# USB_Type_C.net
KiCad netlist of a schematic drawn in Altium Designer
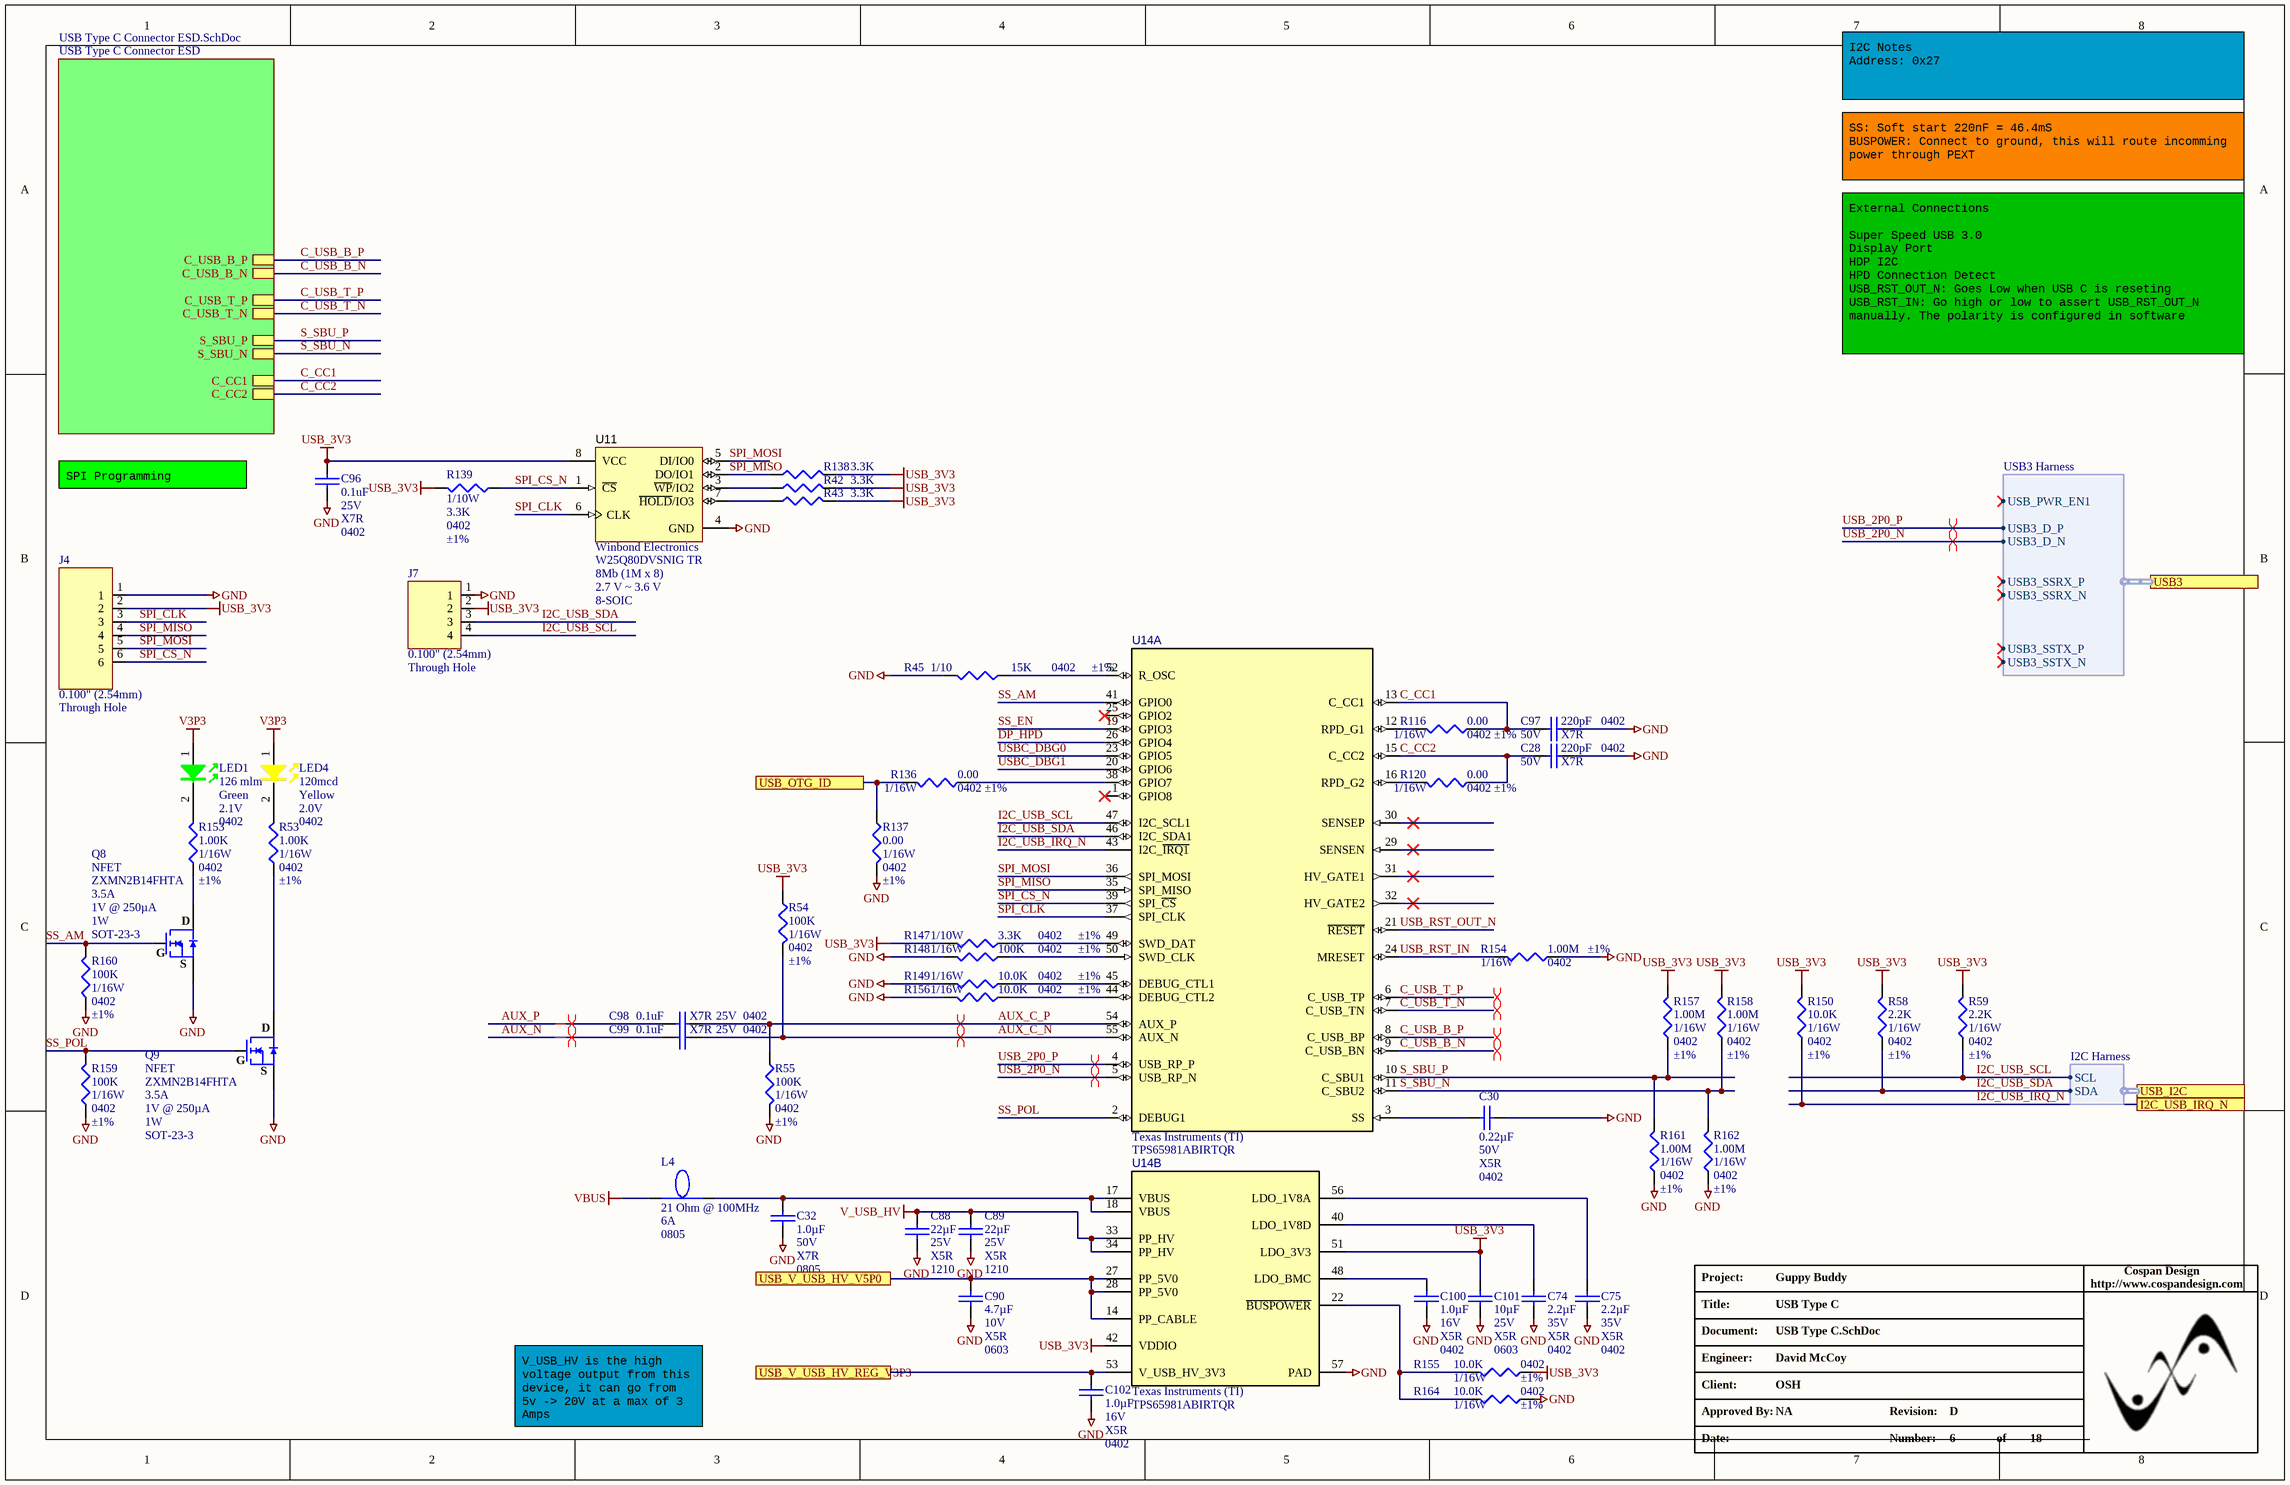
[diagram p0: USB Type C.SchDoc]

(export (version "E")
  (design (tool "Eeschema 10.0.6"))
  (components
    (comp (ref "C28")
      (value "220pF")
      (footprint "C_0402")
      (description "CAP CER 220PF 50V 10% X7R 0402")
      (fields
        (field (name "MANUFACTURER") "Murata Electronics North America")
        (field (name "MANUFACTURER PART NUMBER") "GRM155R71H221KA01D")
        (field (name "CAPACITANCE") "220pF")
        (field (name "VOLTAGE - RATED") "50V")
        (field (name "TEMPERATURE COEFFICIENT") "X7R")
        (field (name "PACKAGE / CASE") "0402")
      )
      (libsource (lib "Main Library") (part "C_0402_220PF_50V"))
    )
    (comp (ref "C30")
      (value "C_0402_0.22UF_50V")
      (footprint "C_ERA-0402")
      (description "CAP CER 0.22UF 50V X5R 0402")
      (fields
        (field (name "MANUFACTURER") "Taiyo Yuden")
        (field (name "MANUFACTURER PART NUMBER") "UMK105BJ224KV-F")
        (field (name "CAPACITANCE") "0.22µF")
        (field (name "VOLTAGE - RATED") "50V")
        (field (name "TEMPERATURE COEFFICIENT") "X5R")
        (field (name "PACKAGE / CASE") "0402")
      )
      (libsource (lib "Main Library") (part "C_0402_0.22UF_50V"))
    )
    (comp (ref "C32")
      (value "1.0uF")
      (footprint "C_ERA-0805")
      (description "CAP CER 1UF 50V X7R 0805")
      (fields
        (field (name "TOLERANCE") "10%")
        (field (name "CAPACITANCE") "1.0µF")
        (field (name "VOLTAGE - RATED") "50V")
        (field (name "TEMPERATURE COEFFICIENT") "X7R")
        (field (name "PACKAGE / CASE") "0805")
        (field (name "VOLTAGE") "50V")
      )
      (libsource (lib "Main LibraryX") (part "C_0805_1.0uF_50V"))
    )
    (comp (ref "C74")
      (value "C_0402_2.2uF_35V")
      (footprint "C_ERA-0402")
      (description "CAP CER 2.2UF 35V 20% X5R 0402")
      (fields
        (field (name "MANUFACTURER") "TDK Corporation")
        (field (name "MANUFACTURER PART NUMBER") "C1005X5R1V225K050BC")
        (field (name "CAPACITANCE") "2.2µF")
        (field (name "VOLTAGE - RATED") "35V")
        (field (name "TEMPERATURE COEFFICIENT") "X5R")
        (field (name "PACKAGE / CASE") "0402")
      )
      (libsource (lib "Main Library") (part "C_0402_2.2uF_35V"))
    )
    (comp (ref "C75")
      (value "C_0402_2.2uF_35V")
      (footprint "C_ERA-0402")
      (description "CAP CER 2.2UF 35V 20% X5R 0402")
      (fields
        (field (name "MANUFACTURER") "TDK Corporation")
        (field (name "MANUFACTURER PART NUMBER") "C1005X5R1V225K050BC")
        (field (name "CAPACITANCE") "2.2µF")
        (field (name "VOLTAGE - RATED") "35V")
        (field (name "TEMPERATURE COEFFICIENT") "X5R")
        (field (name "PACKAGE / CASE") "0402")
      )
      (libsource (lib "Main Library") (part "C_0402_2.2uF_35V"))
    )
    (comp (ref "C88")
      (value "22µF")
      (footprint "C_14-1210")
      (description "CAP CER 22UF 25V 20% X5R 1210")
      (fields
        (field (name "MANUFACTURER") "Taiyo Yuden")
        (field (name "MANUFACTURER PART NUMBER") "TMK325BJ226MM-T")
        (field (name "CAPACITANCE") "22µF")
        (field (name "VOLTAGE - RATED") "25V")
        (field (name "TEMPERATURE COEFFICIENT") "X5R")
        (field (name "PACKAGE / CASE") "1210")
      )
      (libsource (lib "Main Library") (part "C_1210_22µF"))
    )
    (comp (ref "C89")
      (value "22µF")
      (footprint "C_14-1210")
      (description "CAP CER 22UF 25V 20% X5R 1210")
      (fields
        (field (name "MANUFACTURER") "Taiyo Yuden")
        (field (name "MANUFACTURER PART NUMBER") "TMK325BJ226MM-T")
        (field (name "CAPACITANCE") "22µF")
        (field (name "VOLTAGE - RATED") "25V")
        (field (name "TEMPERATURE COEFFICIENT") "X5R")
        (field (name "PACKAGE / CASE") "1210")
      )
      (libsource (lib "Main Library") (part "C_1210_22µF"))
    )
    (comp (ref "C90")
      (value "4.7µF")
      (footprint "C_0603")
      (description "CAP CER 4.7UF 10V X5R 0603")
      (fields
        (field (name "TOLERANCE") "10%")
        (field (name "CAPACITANCE") "4.7µF")
        (field (name "VOLTAGE - RATED") "10V")
        (field (name "TEMPERATURE COEFFICIENT") "X5R")
        (field (name "PACKAGE / CASE") "0603")
        (field (name "VOLTAGE") "35V")
      )
      (libsource (lib "Main LibraryX") (part "C_0603_4.7uF_10V"))
    )
    (comp (ref "C96")
      (value "C_0402_0.1UF_25V")
      (footprint "C_0402")
      (description "CAP CER 0.1UF 25V X6S 0402")
      (fields
        (field (name "TOLERANCE") "10%")
        (field (name "CAPACITANCE") "0.1uF")
        (field (name "VOLTAGE - RATED") "25V")
        (field (name "TEMPERATURE COEFFICIENT") "X7R")
        (field (name "PACKAGE / CASE") "0402")
      )
      (libsource (lib "Cospan Design") (part "C_0402_0.1UF_25V"))
    )
    (comp (ref "C97")
      (value "220pF")
      (footprint "C_0402")
      (description "CAP CER 220PF 50V 10% X7R 0402")
      (fields
        (field (name "MANUFACTURER") "Murata Electronics North America")
        (field (name "MANUFACTURER PART NUMBER") "GRM155R71H221KA01D")
        (field (name "CAPACITANCE") "220pF")
        (field (name "VOLTAGE - RATED") "50V")
        (field (name "TEMPERATURE COEFFICIENT") "X7R")
        (field (name "PACKAGE / CASE") "0402")
      )
      (libsource (lib "Main Library") (part "C_0402_220PF_50V"))
    )
    (comp (ref "C98")
      (value "C_0402_0.1UF_25V")
      (footprint "C_0402")
      (description "CAP CER 0.1UF 25V X6S 0402")
      (fields
        (field (name "TOLERANCE") "10%")
        (field (name "CAPACITANCE") "0.1uF")
        (field (name "VOLTAGE - RATED") "25V")
        (field (name "TEMPERATURE COEFFICIENT") "X7R")
        (field (name "PACKAGE / CASE") "0402")
      )
      (libsource (lib "Cospan Design") (part "C_0402_0.1UF_25V"))
    )
    (comp (ref "C99")
      (value "C_0402_0.1UF_25V")
      (footprint "C_0402")
      (description "CAP CER 0.1UF 25V X6S 0402")
      (fields
        (field (name "TOLERANCE") "10%")
        (field (name "CAPACITANCE") "0.1uF")
        (field (name "VOLTAGE - RATED") "25V")
        (field (name "TEMPERATURE COEFFICIENT") "X7R")
        (field (name "PACKAGE / CASE") "0402")
      )
      (libsource (lib "Cospan Design") (part "C_0402_0.1UF_25V"))
    )
    (comp (ref "C100")
      (value "1.0uF")
      (footprint "C_0402")
      (description "CAP CER 1.0UF 16V X5R 0402")
      (fields
        (field (name "TOLERANCE") "10%")
        (field (name "CAPACITANCE") "1.0µF")
        (field (name "VOLTAGE - RATED") "16V")
        (field (name "TEMPERATURE COEFFICIENT") "X5R")
        (field (name "PACKAGE / CASE") "0402")
        (field (name "VOLTAGE") "16V")
      )
      (libsource (lib "Main LibraryX") (part "C_0402_1.0UF_16V"))
    )
    (comp (ref "C101")
      (value "C_0603_10µF")
      (footprint "C_ERA-0603")
      (description "CAP CER 10UF 16V X5R 0603")
      (fields
        (field (name "MANUFACTURER") "Murata Electronics North America")
        (field (name "MANUFACTURER PART NUMBER") "GRM188R61C106MA73D")
        (field (name "CAPACITANCE") "10µF")
        (field (name "VOLTAGE - RATED") "25V")
        (field (name "TEMPERATURE COEFFICIENT") "X5R")
        (field (name "PACKAGE / CASE") "0603")
      )
      (libsource (lib "Cospan Design") (part "C_0603_10µF"))
    )
    (comp (ref "C102")
      (value "1.0uF")
      (footprint "C_0402")
      (description "CAP CER 1.0UF 16V X5R 0402")
      (fields
        (field (name "TOLERANCE") "10%")
        (field (name "CAPACITANCE") "1.0µF")
        (field (name "VOLTAGE - RATED") "16V")
        (field (name "TEMPERATURE COEFFICIENT") "X5R")
        (field (name "PACKAGE / CASE") "0402")
        (field (name "VOLTAGE") "16V")
      )
      (libsource (lib "Main LibraryX") (part "C_0402_1.0UF_16V"))
    )
    (comp (ref "J4")
      (value "J_HDR1X6_THRHOLE_VERT")
      (footprint "HDR_1X6")
      (description "CONN HEADER .100\" 12POS TIN PCB")
      (fields
        (field (name "MANUFACTURER") "Samtec")
        (field (name "MANUFACTURER PART NUMBER") "TSW-106-07-T-S")
        (field (name "PITCH") "0.100\" (2.54mm)")
        (field (name "MOUNTING TYPE") "Through Hole")
      )
      (libsource (lib "Main Library") (part "J_HDR1X6_THRHOLE_VERT"))
    )
    (comp (ref "J7")
      (value "J_HDR1X4_THRHOLE_VERT")
      (footprint "HDR_1X4")
      (description "CONN HEADER .100\" 4POS TIN PCB")
      (fields
        (field (name "MANUFACTURER") "Samtec")
        (field (name "MANUFACTURER PART NUMBER") "TSW-104-07-T-S")
        (field (name "PITCH") "0.100\" (2.54mm)")
        (field (name "MOUNTING TYPE") "Through Hole")
      )
      (libsource (lib "Main Library") (part "J_HDR1X4_THRHOLE_VERT"))
    )
    (comp (ref "L4")
      (value "L_FB_21OHM_100MHZ")
      (footprint "C_ERA-0805")
      (description "FERRITE BEAD 21 OHM 0805 1LN")
      (fields
        (field (name "MANUFACTURER") "Taiyo Yuden")
        (field (name "MANUFACTURER PART NUMBER") "FBMJ2125HM210NT")
        (field (name "IMPEDANCE @ FREQUENCY") "21 Ohm @ 100MHz")
        (field (name "CURRENT RATING") "6A")
        (field (name "PACKAGE / CASE") "0805")
      )
      (libsource (lib "Main Library") (part "L_FB_21OHM_100MHZ"))
    )
    (comp (ref "LED1")
      (value "LED_GRN_0402")
      (footprint "DIOM1005X07L_GREEN")
      (description "LED 1X0.5MM 570NM GN WTR CLR SMD")
      (fields
        (field (name "MANUFACTURER") "Kingbright Corp")
        (field (name "MANUFACTURER PART NUMBER") "APHHS1005CGCK")
        (field (name "LUMINOUS FLUX @ CURRENT - TEST") "126 mlm")
        (field (name "COLOR") "Green")
        (field (name "VOLTAGE - FORWARD (VF) TYP") "2.1V")
        (field (name "PACKAGE / CASE") "0402")
      )
      (libsource (lib "Main Library") (part "LED_GRN_0402"))
    )
    (comp (ref "LED4")
      (value "LED_YLW_0402")
      (footprint "DIOM1005X07L_YELLOW")
      (description "LED 1X0.5MM 590NM YW WTR CLR SMD")
      (fields
        (field (name "MANUFACTURER") "Kingbright Corp")
        (field (name "MANUFACTURER PART NUMBER") "APHHS1005SYCK")
        (field (name "MILLICANDELA RATING") "120mcd")
        (field (name "COLOR") "Yellow")
        (field (name "VOLTAGE - FORWARD (VF) TYP") "2.0V")
        (field (name "PACKAGE / CASE") "0402")
      )
      (libsource (lib "Main Library") (part "LED_YLW_0402"))
    )
    (comp (ref "Q8")
      (value "NFET")
      (footprint "SOT-23A")
      (description "MOSFET N-CH 20V 3.5A SOT23-3")
      (fields
        (field (name "MANUFACTURER") "Diodes Incorporated")
        (field (name "MANUFACTURER PART NUMBER") "ZXMN2B14FHTA")
        (field (name "CURRENT - CONTINUOUS DRAIN (ID) @ 25° C") "3.5A")
        (field (name "VGS(TH) (MAX) @ ID") "1V @ 250µA")
        (field (name "POWER - MAX") "1W")
        (field (name "PACKAGE / CASE") "SOT-23-3")
      )
      (libsource (lib "Main LibraryX") (part "Q_NFET_3.50A_SOT23"))
    )
    (comp (ref "Q9")
      (value "NFET")
      (footprint "SOT-23A")
      (description "MOSFET N-CH 20V 3.5A SOT23-3")
      (fields
        (field (name "MANUFACTURER") "Diodes Incorporated")
        (field (name "MANUFACTURER PART NUMBER") "ZXMN2B14FHTA")
        (field (name "CURRENT - CONTINUOUS DRAIN (ID) @ 25° C") "3.5A")
        (field (name "VGS(TH) (MAX) @ ID") "1V @ 250µA")
        (field (name "POWER - MAX") "1W")
        (field (name "PACKAGE / CASE") "SOT-23-3")
      )
      (libsource (lib "Main LibraryX") (part "Q_NFET_3.50A_SOT23"))
    )
    (comp (ref "R42")
      (value "3.3k Ohms")
      (footprint "R_0402")
      (description "RES 3.30K OHM 1/10W 1% 0402 SM")
      (fields
        (field (name "MANUFACTURER") "Panasonic - ECG")
        (field (name "MANUFACTURER PART NUMBER") "ERJ-2RKF3301X")
        (field (name "RESISTANCE IN OHMS") "3.3K")
      )
      (libsource (lib "Main Library") (part "R_0402_3.3K"))
    )
    (comp (ref "R43")
      (value "3.3k Ohms")
      (footprint "R_0402")
      (description "RES 3.30K OHM 1/10W 1% 0402 SM")
      (fields
        (field (name "MANUFACTURER") "Panasonic - ECG")
        (field (name "MANUFACTURER PART NUMBER") "ERJ-2RKF3301X")
        (field (name "RESISTANCE IN OHMS") "3.3K")
      )
      (libsource (lib "Main Library") (part "R_0402_3.3K"))
    )
    (comp (ref "R45")
      (value "R_0402_15.0K")
      (footprint "R_0402")
      (description "RES 15.0K OHM 1/10W 1% 0402 SMD")
      (fields
        (field (name "MANUFACTURER") "Panasonic - ECG")
        (field (name "MANUFACTURER PART NUMBER") "ERJ-2RKF1502X")
        (field (name "RESISTANCE IN OHMS") "15K")
        (field (name "POWER (WATTS)") "1/10")
        (field (name "CASE") "0402")
        (field (name "TOLERANCE") "±1%")
      )
      (libsource (lib "Main Library") (part "R_0402_15.0K"))
    )
    (comp (ref "R53")
      (value "1.0k Ohms")
      (footprint "R_0402")
      (description "RES 1.00K OHM 1/16W 1% 0402 SMD")
      (fields
        (field (name "MANUFACTURER") "Yageo")
        (field (name "MANUFACTURER PART NUMBER") "RC0402FR-071KL")
        (field (name "RESISTANCE IN OHMS") "1.00K")
        (field (name "POWER (WATTS)") "1/16W")
        (field (name "CASE") "0402")
        (field (name "TOLERANCE") "±1%")
      )
      (libsource (lib "Main Library") (part "R_0402_1.0K"))
    )
    (comp (ref "R54")
      (value "R_0402_100K")
      (footprint "R_0402")
      (description "RES SMD 100K OHM 1% 1/16W 0402")
      (fields
        (field (name "MANUFACTURER") "Yageo")
        (field (name "MANUFACTURER PART NUMBER") "RC0402FR-07100KL")
        (field (name "RESISTANCE IN OHMS") "100K")
        (field (name "POWER (WATTS)") "1/16W")
        (field (name "CASE") "0402")
        (field (name "TOLERANCE") "±1%")
      )
      (libsource (lib "Cospan Design") (part "R_0402_100K"))
    )
    (comp (ref "R55")
      (value "R_0402_100K")
      (footprint "R_0402")
      (description "RES SMD 100K OHM 1% 1/16W 0402")
      (fields
        (field (name "MANUFACTURER") "Yageo")
        (field (name "MANUFACTURER PART NUMBER") "RC0402FR-07100KL")
        (field (name "RESISTANCE IN OHMS") "100K")
        (field (name "POWER (WATTS)") "1/16W")
        (field (name "CASE") "0402")
        (field (name "TOLERANCE") "±1%")
      )
      (libsource (lib "Cospan Design") (part "R_0402_100K"))
    )
    (comp (ref "R58")
      (value "R_0402_2.2K")
      (footprint "R_0402")
      (description "RES SMD 2.2K OHM 1% 1/10W 0402")
      (fields
        (field (name "MANUFACTURER") "Panasonic Electronic Components")
        (field (name "MANUFACTURER PART NUMBER") "ERJ-2RKF2201X")
        (field (name "RESISTANCE IN OHMS") "2.2K")
        (field (name "POWER (WATTS)") "1/16W")
        (field (name "CASE") "0402")
        (field (name "TOLERANCE") "±1%")
      )
      (libsource (lib "Cospan Design") (part "R_0402_2.2K"))
    )
    (comp (ref "R59")
      (value "R_0402_2.2K")
      (footprint "R_0402")
      (description "RES SMD 2.2K OHM 1% 1/10W 0402")
      (fields
        (field (name "MANUFACTURER") "Panasonic Electronic Components")
        (field (name "MANUFACTURER PART NUMBER") "ERJ-2RKF2201X")
        (field (name "RESISTANCE IN OHMS") "2.2K")
        (field (name "POWER (WATTS)") "1/16W")
        (field (name "CASE") "0402")
        (field (name "TOLERANCE") "±1%")
      )
      (libsource (lib "Cospan Design") (part "R_0402_2.2K"))
    )
    (comp (ref "R116")
      (value "0.0 Ohms")
      (footprint "R_0402")
      (description "RES 0.00 OHM 1/16W 1% 0402 SMD")
      (fields
        (field (name "MANUFACTURER") "Yageo")
        (field (name "MANUFACTURER PART NUMBER") "RC0402JR-070RL")
        (field (name "RESISTANCE IN OHMS") "0.00")
        (field (name "POWER (WATTS)") "1/16W")
        (field (name "CASE") "0402")
        (field (name "TOLERANCE") "±1%")
      )
      (libsource (lib "Cospan Design") (part "R_0402_0.00"))
    )
    (comp (ref "R120")
      (value "0.0 Ohms")
      (footprint "R_0402")
      (description "RES 0.00 OHM 1/16W 1% 0402 SMD")
      (fields
        (field (name "MANUFACTURER") "Yageo")
        (field (name "MANUFACTURER PART NUMBER") "RC0402JR-070RL")
        (field (name "RESISTANCE IN OHMS") "0.00")
        (field (name "POWER (WATTS)") "1/16W")
        (field (name "CASE") "0402")
        (field (name "TOLERANCE") "±1%")
      )
      (libsource (lib "Cospan Design") (part "R_0402_0.00"))
    )
    (comp (ref "R136")
      (value "0.0 Ohms")
      (footprint "R_0402")
      (description "RES 0.00 OHM 1/16W 1% 0402 SMD")
      (fields
        (field (name "MANUFACTURER") "Yageo")
        (field (name "MANUFACTURER PART NUMBER") "RC0402JR-070RL")
        (field (name "RESISTANCE IN OHMS") "0.00")
        (field (name "POWER (WATTS)") "1/16W")
        (field (name "CASE") "0402")
        (field (name "TOLERANCE") "±1%")
      )
      (libsource (lib "Cospan Design") (part "R_0402_0.00"))
    )
    (comp (ref "R137")
      (value "0.0 Ohms")
      (footprint "R_0402")
      (description "RES 0.00 OHM 1/16W 1% 0402 SMD")
      (fields
        (field (name "MANUFACTURER") "Yageo")
        (field (name "MANUFACTURER PART NUMBER") "RC0402JR-070RL")
        (field (name "RESISTANCE IN OHMS") "0.00")
        (field (name "POWER (WATTS)") "1/16W")
        (field (name "CASE") "0402")
        (field (name "TOLERANCE") "±1%")
      )
      (libsource (lib "Cospan Design") (part "R_0402_0.00"))
    )
    (comp (ref "R138")
      (value "3.3k Ohms")
      (footprint "R_0402")
      (description "RES 3.30K OHM 1/10W 1% 0402 SM")
      (fields
        (field (name "MANUFACTURER") "Panasonic - ECG")
        (field (name "MANUFACTURER PART NUMBER") "ERJ-2RKF3301X")
        (field (name "RESISTANCE IN OHMS") "3.3K")
      )
      (libsource (lib "Main Library") (part "R_0402_3.3K"))
    )
    (comp (ref "R139")
      (value "3.3k Ohms")
      (footprint "R_0402")
      (description "RES 3.30K OHM 1/10W 1% 0402 SM")
      (fields
        (field (name "MANUFACTURER") "Panasonic - ECG")
        (field (name "MANUFACTURER PART NUMBER") "ERJ-2RKF3301X")
        (field (name "POWER (WATTS)") "1/10W")
        (field (name "RESISTANCE IN OHMS") "3.3K")
        (field (name "CASE") "0402")
        (field (name "TOLERANCE") "±1%")
      )
      (libsource (lib "Main Library") (part "R_0402_3.3K"))
    )
    (comp (ref "R147")
      (value "3.3k Ohms")
      (footprint "R_0402")
      (description "RES 3.30K OHM 1/10W 1% 0402 SM")
      (fields
        (field (name "MANUFACTURER") "Panasonic - ECG")
        (field (name "MANUFACTURER PART NUMBER") "ERJ-2RKF3301X")
        (field (name "POWER (WATTS)") "1/10W")
        (field (name "RESISTANCE IN OHMS") "3.3K")
        (field (name "CASE") "0402")
        (field (name "TOLERANCE") "±1%")
      )
      (libsource (lib "Main Library") (part "R_0402_3.3K"))
    )
    (comp (ref "R148")
      (value "R_0402_100K")
      (footprint "R_0402")
      (description "RES SMD 100K OHM 1% 1/16W 0402")
      (fields
        (field (name "MANUFACTURER") "Yageo")
        (field (name "MANUFACTURER PART NUMBER") "RC0402FR-07100KL")
        (field (name "RESISTANCE IN OHMS") "100K")
        (field (name "POWER (WATTS)") "1/16W")
        (field (name "CASE") "0402")
        (field (name "TOLERANCE") "±1%")
      )
      (libsource (lib "Cospan Design") (part "R_0402_100K"))
    )
    (comp (ref "R149")
      (value "R_0402_10.0K")
      (footprint "R_0402")
      (description "RES 10.0K OHM 1/16W 1% 0402 SMD")
      (fields
        (field (name "MANUFACTURER") "Stackpole Electronics Inc")
        (field (name "MANUFACTURER PART NUMBER") "RMCF0402FT10K0")
        (field (name "RESISTANCE IN OHMS") "10.0K")
        (field (name "POWER (WATTS)") "1/16W")
        (field (name "CASE") "0402")
        (field (name "TOLERANCE") "±1%")
      )
      (libsource (lib "Cospan Design") (part "R_0402_10.0K"))
    )
    (comp (ref "R150")
      (value "R_0402_10.0K")
      (footprint "R_0402")
      (description "RES 10.0K OHM 1/16W 1% 0402 SMD")
      (fields
        (field (name "MANUFACTURER") "Stackpole Electronics Inc")
        (field (name "MANUFACTURER PART NUMBER") "RMCF0402FT10K0")
        (field (name "RESISTANCE IN OHMS") "10.0K")
        (field (name "POWER (WATTS)") "1/16W")
        (field (name "CASE") "0402")
        (field (name "TOLERANCE") "±1%")
      )
      (libsource (lib "Cospan Design") (part "R_0402_10.0K"))
    )
    (comp (ref "R153")
      (value "1.0k Ohms")
      (footprint "R_0402")
      (description "RES 1.00K OHM 1/16W 1% 0402 SMD")
      (fields
        (field (name "MANUFACTURER") "Yageo")
        (field (name "MANUFACTURER PART NUMBER") "RC0402FR-071KL")
        (field (name "RESISTANCE IN OHMS") "1.00K")
        (field (name "POWER (WATTS)") "1/16W")
        (field (name "CASE") "0402")
        (field (name "TOLERANCE") "±1%")
      )
      (libsource (lib "Main Library") (part "R_0402_1.0K"))
    )
    (comp (ref "R154")
      (value "1.0M Ohms")
      (footprint "R_0402")
      (description "RES 1.00M OHM 1/16W 1% 0402 SMD")
      (fields
        (field (name "MANUFACTURER") "Vishay/Dale")
        (field (name "MANUFACTURER PART NUMBER") "CRCW04021M00FKED")
        (field (name "RESISTANCE IN OHMS") "1.00M")
        (field (name "POWER (WATTS)") "1/16W")
        (field (name "CASE") "0402")
        (field (name "TOLERANCE") "±1%")
      )
      (libsource (lib "Main Library") (part "R_0402_1.0M"))
    )
    (comp (ref "R155")
      (value "R_0402_10.0K")
      (footprint "R_0402")
      (description "RES 10.0K OHM 1/16W 1% 0402 SMD")
      (fields
        (field (name "MANUFACTURER") "Stackpole Electronics Inc")
        (field (name "MANUFACTURER PART NUMBER") "RMCF0402FT10K0")
        (field (name "RESISTANCE IN OHMS") "10.0K")
        (field (name "POWER (WATTS)") "1/16W")
        (field (name "CASE") "0402")
        (field (name "TOLERANCE") "±1%")
      )
      (libsource (lib "Cospan Design") (part "R_0402_10.0K"))
    )
    (comp (ref "R156")
      (value "R_0402_10.0K")
      (footprint "R_0402")
      (description "RES 10.0K OHM 1/16W 1% 0402 SMD")
      (fields
        (field (name "MANUFACTURER") "Stackpole Electronics Inc")
        (field (name "MANUFACTURER PART NUMBER") "RMCF0402FT10K0")
        (field (name "RESISTANCE IN OHMS") "10.0K")
        (field (name "POWER (WATTS)") "1/16W")
        (field (name "CASE") "0402")
        (field (name "TOLERANCE") "±1%")
      )
      (libsource (lib "Cospan Design") (part "R_0402_10.0K"))
    )
    (comp (ref "R157")
      (value "1.0M Ohms")
      (footprint "R_0402")
      (description "RES 1.00M OHM 1/16W 1% 0402 SMD")
      (fields
        (field (name "MANUFACTURER") "Vishay/Dale")
        (field (name "MANUFACTURER PART NUMBER") "CRCW04021M00FKED")
        (field (name "RESISTANCE IN OHMS") "1.00M")
        (field (name "POWER (WATTS)") "1/16W")
        (field (name "CASE") "0402")
        (field (name "TOLERANCE") "±1%")
      )
      (libsource (lib "Main Library") (part "R_0402_1.0M"))
    )
    (comp (ref "R158")
      (value "1.0M Ohms")
      (footprint "R_0402")
      (description "RES 1.00M OHM 1/16W 1% 0402 SMD")
      (fields
        (field (name "MANUFACTURER") "Vishay/Dale")
        (field (name "MANUFACTURER PART NUMBER") "CRCW04021M00FKED")
        (field (name "RESISTANCE IN OHMS") "1.00M")
        (field (name "POWER (WATTS)") "1/16W")
        (field (name "CASE") "0402")
        (field (name "TOLERANCE") "±1%")
      )
      (libsource (lib "Main Library") (part "R_0402_1.0M"))
    )
    (comp (ref "R159")
      (value "R_0402_100.0K")
      (footprint "R_0402")
      (description "RES 100K OHM 1/16W 1% 0402 SMD")
      (fields
        (field (name "MANUFACTURER") "Stackpole Electronics Inc")
        (field (name "MANUFACTURER PART NUMBER") "RMCF0402FT100K")
        (field (name "RESISTANCE IN OHMS") "100K")
        (field (name "POWER (WATTS)") "1/16W")
        (field (name "CASE") "0402")
        (field (name "TOLERANCE") "±1%")
      )
      (libsource (lib "Main Library") (part "R_0402_100.0K"))
    )
    (comp (ref "R160")
      (value "R_0402_100.0K")
      (footprint "R_0402")
      (description "RES 100K OHM 1/16W 1% 0402 SMD")
      (fields
        (field (name "MANUFACTURER") "Stackpole Electronics Inc")
        (field (name "MANUFACTURER PART NUMBER") "RMCF0402FT100K")
        (field (name "RESISTANCE IN OHMS") "100K")
        (field (name "POWER (WATTS)") "1/16W")
        (field (name "CASE") "0402")
        (field (name "TOLERANCE") "±1%")
      )
      (libsource (lib "Main Library") (part "R_0402_100.0K"))
    )
    (comp (ref "R161")
      (value "1.0M Ohms")
      (footprint "R_0402")
      (description "RES 1.00M OHM 1/16W 1% 0402 SMD")
      (fields
        (field (name "MANUFACTURER") "Vishay/Dale")
        (field (name "MANUFACTURER PART NUMBER") "CRCW04021M00FKED")
        (field (name "RESISTANCE IN OHMS") "1.00M")
        (field (name "POWER (WATTS)") "1/16W")
        (field (name "CASE") "0402")
        (field (name "TOLERANCE") "±1%")
      )
      (libsource (lib "Main Library") (part "R_0402_1.0M"))
    )
    (comp (ref "R162")
      (value "1.0M Ohms")
      (footprint "R_0402")
      (description "RES 1.00M OHM 1/16W 1% 0402 SMD")
      (fields
        (field (name "MANUFACTURER") "Vishay/Dale")
        (field (name "MANUFACTURER PART NUMBER") "CRCW04021M00FKED")
        (field (name "RESISTANCE IN OHMS") "1.00M")
        (field (name "POWER (WATTS)") "1/16W")
        (field (name "CASE") "0402")
        (field (name "TOLERANCE") "±1%")
      )
      (libsource (lib "Main Library") (part "R_0402_1.0M"))
    )
    (comp (ref "R164")
      (value "R_0402_10.0K")
      (footprint "R_0402")
      (description "RES 10.0K OHM 1/16W 1% 0402 SMD")
      (fields
        (field (name "MANUFACTURER") "Stackpole Electronics Inc")
        (field (name "MANUFACTURER PART NUMBER") "RMCF0402FT10K0")
        (field (name "RESISTANCE IN OHMS") "10.0K")
        (field (name "POWER (WATTS)") "1/16W")
        (field (name "CASE") "0402")
        (field (name "TOLERANCE") "±1%")
      )
      (libsource (lib "Cospan Design") (part "R_0402_10.0K"))
    )
    (comp (ref "U11")
      (value "U_W25Q80DVSNIG")
      (footprint "SOIC-8 - TI")
      (description "3V, 8Mbit, Serial Flash Memory with Dual and Qual SPI, SOIC-8")
      (fields
        (field (name "MANUFACTURER") "Winbond Electronics")
        (field (name "MANUFACTURER PART NUMBER") "W25Q80DVSNIG TR")
        (field (name "MEMORY SIZE") "8Mb (1M x 8)")
        (field (name "VOLTAGE - SUPPLY") "2.7 V ~ 3.6 V")
        (field (name "SUPPLIER DEVICE PACKAGE") "8-SOIC")
      )
      (libsource (lib "Cospan Design") (part "U_W25Q80DVSNIG"))
    )
    (comp (ref "U14")
      (value "~")
      (footprint "RWE0056B")
      (description "USB, Type-C Controller PMIC 56-QFN (8x8)")
      (fields
        (field (name "MANUFACTURER") "Texas Instruments (TI)")
        (field (name "MANUFACTURER PART NUMBER") "TPS65981ABIRTQR")
      )
      (libsource (lib "Cospan Design") (part "U_TPS65981ABQWRWERQ1"))
    )
  )
  (nets
    (net (code "4") (name "/AUX_C_N") (class "Default")
      (node (ref "C99") (pin "1") (pinfunction "1_1") (pintype "passive"))
      (node (ref "R54") (pin "1") (pinfunction "1_1") (pintype "passive"))
      (node (ref "U14") (pin "55") (pinfunction "AUX_N_55") (pintype "bidirectional"))
    )
    (net (code "5") (name "/AUX_C_P") (class "Default")
      (node (ref "C98") (pin "1") (pinfunction "1_1") (pintype "passive"))
      (node (ref "R55") (pin "2") (pinfunction "2_2") (pintype "passive"))
      (node (ref "U14") (pin "54") (pinfunction "AUX_P_54") (pintype "bidirectional"))
    )
    (net (code "6") (name "/AUX_N") (class "Default")
      (node (ref "C99") (pin "2") (pinfunction "2_2") (pintype "passive"))
    )
    (net (code "7") (name "/AUX_P") (class "Default")
      (node (ref "C98") (pin "2") (pinfunction "2_2") (pintype "passive"))
    )
    (net (code "8") (name "/C_CC1") (class "Default")
      (node (ref "C97") (pin "2") (pinfunction "2_2") (pintype "passive"))
      (node (ref "R116") (pin "2") (pinfunction "2_2") (pintype "passive"))
      (node (ref "U14") (pin "13") (pinfunction "C_CC1_13") (pintype "bidirectional"))
    )
    (net (code "9") (name "/C_CC2") (class "Default")
      (node (ref "C28") (pin "2") (pinfunction "2_2") (pintype "passive"))
      (node (ref "R120") (pin "2") (pinfunction "2_2") (pintype "passive"))
      (node (ref "U14") (pin "15") (pinfunction "C_CC2_15") (pintype "bidirectional"))
    )
    (net (code "10") (name "/C_USB_B_N") (class "Default")
      (node (ref "U14") (pin "9") (pinfunction "C_USB_BN_9") (pintype "bidirectional"))
    )
    (net (code "11") (name "/C_USB_B_P") (class "Default")
      (node (ref "U14") (pin "8") (pinfunction "C_USB_BP_8") (pintype "bidirectional"))
    )
    (net (code "12") (name "/C_USB_T_N") (class "Default")
      (node (ref "U14") (pin "7") (pinfunction "C_USB_TN_7") (pintype "bidirectional"))
    )
    (net (code "13") (name "/C_USB_T_P") (class "Default")
      (node (ref "U14") (pin "6") (pinfunction "C_USB_TP_6") (pintype "bidirectional"))
    )
    (net (code "14") (name "/DP_HPD") (class "Default")
      (node (ref "U14") (pin "26") (pinfunction "GPIO4_26") (pintype "bidirectional"))
    )
    (net (code "15") (name "/I2C_USB_IRQ_N") (class "Default")
      (node (ref "R150") (pin "2") (pinfunction "2_2") (pintype "passive"))
      (node (ref "U14") (pin "43") (pinfunction "I2C_~{IRQ1}_43") (pintype "open_collector"))
    )
    (net (code "16") (name "/I2C_USB_SCL") (class "Default")
      (node (ref "J7") (pin "4") (pinfunction "4_4") (pintype "passive"))
      (node (ref "R59") (pin "2") (pinfunction "2_2") (pintype "passive"))
      (node (ref "U14") (pin "47") (pinfunction "I2C_SCL1_47") (pintype "bidirectional"))
    )
    (net (code "17") (name "/I2C_USB_SDA") (class "Default")
      (node (ref "J7") (pin "3") (pinfunction "3_3") (pintype "passive"))
      (node (ref "R58") (pin "2") (pinfunction "2_2") (pintype "passive"))
      (node (ref "U14") (pin "46") (pinfunction "I2C_SDA1_46") (pintype "bidirectional"))
    )
    (net (code "18") (name "/SPI_CLK") (class "Default")
      (node (ref "J4") (pin "3") (pinfunction "3_3") (pintype "passive"))
      (node (ref "U11") (pin "6") (pinfunction "CLK_6") (pintype "input"))
      (node (ref "U14") (pin "37") (pinfunction "SPI_CLK_37") (pintype "output"))
    )
    (net (code "19") (name "/SPI_CS_N") (class "Default")
      (node (ref "J4") (pin "6") (pinfunction "6_6") (pintype "passive"))
      (node (ref "R139") (pin "2") (pinfunction "2_2") (pintype "passive"))
      (node (ref "U11") (pin "1") (pinfunction "CS_1") (pintype "input"))
      (node (ref "U14") (pin "39") (pinfunction "SPI_~{CS}_39") (pintype "output"))
    )
    (net (code "20") (name "/SPI_MISO") (class "Default")
      (node (ref "J4") (pin "4") (pinfunction "4_4") (pintype "passive"))
      (node (ref "R138") (pin "2") (pinfunction "2_2") (pintype "passive"))
      (node (ref "U11") (pin "2") (pinfunction "DO/IO1_2") (pintype "bidirectional"))
      (node (ref "U14") (pin "35") (pinfunction "SPI_MISO_35") (pintype "input"))
    )
    (net (code "21") (name "/SPI_MOSI") (class "Default")
      (node (ref "J4") (pin "5") (pinfunction "5_5") (pintype "passive"))
      (node (ref "U11") (pin "5") (pinfunction "DI/IO0_5") (pintype "bidirectional"))
      (node (ref "U14") (pin "36") (pinfunction "SPI_MOSI_36") (pintype "output"))
    )
    (net (code "22") (name "/SS_AM") (class "Default")
      (node (ref "Q8") (pin "1") (pinfunction "G_1") (pintype "passive"))
      (node (ref "R160") (pin "1") (pinfunction "1_1") (pintype "passive"))
      (node (ref "U14") (pin "41") (pinfunction "GPIO0_41") (pintype "bidirectional"))
    )
    (net (code "23") (name "/SS_EN") (class "Default")
      (node (ref "U14") (pin "19") (pinfunction "GPIO3_19") (pintype "bidirectional"))
    )
    (net (code "24") (name "/SS_POL") (class "Default")
      (node (ref "Q9") (pin "1") (pinfunction "G_1") (pintype "passive"))
      (node (ref "R159") (pin "1") (pinfunction "1_1") (pintype "passive"))
      (node (ref "U14") (pin "2") (pinfunction "DEBUG1_2") (pintype "bidirectional"))
    )
    (net (code "25") (name "/S_SBU_N") (class "Default")
      (node (ref "R158") (pin "2") (pinfunction "2_2") (pintype "passive"))
      (node (ref "R162") (pin "1") (pinfunction "1_1") (pintype "passive"))
      (node (ref "U14") (pin "11") (pinfunction "C_SBU2_11") (pintype "bidirectional"))
    )
    (net (code "26") (name "/S_SBU_P") (class "Default")
      (node (ref "R157") (pin "2") (pinfunction "2_2") (pintype "passive"))
      (node (ref "R161") (pin "1") (pinfunction "1_1") (pintype "passive"))
      (node (ref "U14") (pin "10") (pinfunction "C_SBU1_10") (pintype "bidirectional"))
    )
    (net (code "27") (name "/USBC_DBG0") (class "Default")
      (node (ref "U14") (pin "23") (pinfunction "GPIO5_23") (pintype "bidirectional"))
    )
    (net (code "28") (name "/USBC_DBG1") (class "Default")
      (node (ref "U14") (pin "20") (pinfunction "GPIO6_20") (pintype "bidirectional"))
    )
    (net (code "29") (name "/USB_2P0_N") (class "Default")
      (node (ref "U14") (pin "5") (pinfunction "USB_RP_N_5") (pintype "bidirectional"))
    )
    (net (code "30") (name "/USB_2P0_P") (class "Default")
      (node (ref "U14") (pin "4") (pinfunction "USB_RP_P_4") (pintype "bidirectional"))
    )
    (net (code "31") (name "/USB_OTG_ID") (class "Default")
      (node (ref "R136") (pin "1") (pinfunction "1_1") (pintype "passive"))
      (node (ref "R137") (pin "2") (pinfunction "2_2") (pintype "passive"))
    )
    (net (code "32") (name "/USB_RST_IN") (class "Default")
      (node (ref "R154") (pin "1") (pinfunction "1_1") (pintype "passive"))
      (node (ref "U14") (pin "24") (pinfunction "MRESET_24") (pintype "bidirectional"))
    )
    (net (code "33") (name "/USB_RST_OUT_N") (class "Default")
      (node (ref "U14") (pin "21") (pinfunction "RESET_21") (pintype "bidirectional"))
    )
    (net (code "34") (name "/USB_V_USB_HV_REG_V3P3") (class "Default")
      (node (ref "C102") (pin "2") (pinfunction "2_2") (pintype "passive"))
      (node (ref "U14") (pin "53") (pinfunction "VIN_3V3_53") (pintype "power_in"))
    )
    (net (code "35") (name "/USB_V_USB_HV_V5P0") (class "Default")
      (node (ref "C90") (pin "2") (pinfunction "2_2") (pintype "passive"))
      (node (ref "U14") (pin "14") (pinfunction "PP_CABLE_14") (pintype "power_in"))
      (node (ref "U14") (pin "27") (pinfunction "PP_5V0_27") (pintype "power_in"))
      (node (ref "U14") (pin "28") (pinfunction "PP_5V0_28") (pintype "power_in"))
    )
    (net (code "38") (name "GND") (class "Default")
      (node (ref "C100") (pin "1") (pinfunction "1_1") (pintype "passive"))
      (node (ref "C101") (pin "1") (pinfunction "1_1") (pintype "passive"))
      (node (ref "C102") (pin "1") (pinfunction "1_1") (pintype "passive"))
      (node (ref "C28") (pin "1") (pinfunction "1_1") (pintype "passive"))
      (node (ref "C30") (pin "1") (pinfunction "1_1") (pintype "passive"))
      (node (ref "C32") (pin "1") (pinfunction "1_1") (pintype "passive"))
      (node (ref "C74") (pin "1") (pinfunction "1_1") (pintype "passive"))
      (node (ref "C75") (pin "1") (pinfunction "1_1") (pintype "passive"))
      (node (ref "C88") (pin "1") (pinfunction "1_1") (pintype "passive"))
      (node (ref "C89") (pin "1") (pinfunction "1_1") (pintype "passive"))
      (node (ref "C90") (pin "1") (pinfunction "1_1") (pintype "passive"))
      (node (ref "C96") (pin "1") (pinfunction "1_1") (pintype "passive"))
      (node (ref "C97") (pin "1") (pinfunction "1_1") (pintype "passive"))
      (node (ref "J4") (pin "1") (pinfunction "1_1") (pintype "passive"))
      (node (ref "J7") (pin "1") (pinfunction "1_1") (pintype "passive"))
      (node (ref "Q8") (pin "2") (pinfunction "S_2") (pintype "passive"))
      (node (ref "Q9") (pin "2") (pinfunction "S_2") (pintype "passive"))
      (node (ref "R137") (pin "1") (pinfunction "1_1") (pintype "passive"))
      (node (ref "R148") (pin "1") (pinfunction "1_1") (pintype "passive"))
      (node (ref "R149") (pin "1") (pinfunction "1_1") (pintype "passive"))
      (node (ref "R154") (pin "2") (pinfunction "2_2") (pintype "passive"))
      (node (ref "R156") (pin "1") (pinfunction "1_1") (pintype "passive"))
      (node (ref "R159") (pin "2") (pinfunction "2_2") (pintype "passive"))
      (node (ref "R160") (pin "2") (pinfunction "2_2") (pintype "passive"))
      (node (ref "R161") (pin "2") (pinfunction "2_2") (pintype "passive"))
      (node (ref "R162") (pin "2") (pinfunction "2_2") (pintype "passive"))
      (node (ref "R164") (pin "2") (pinfunction "2_2") (pintype "passive"))
      (node (ref "R45") (pin "1") (pinfunction "1_1") (pintype "passive"))
      (node (ref "R55") (pin "1") (pinfunction "1_1") (pintype "passive"))
      (node (ref "U11") (pin "4") (pinfunction "GND_4") (pintype "power_in"))
      (node (ref "U14") (pin "57") (pinfunction "PAD_57") (pintype "power_in"))
    )
    (net (code "39") (name "Net-(C32-Pad2)") (class "Default")
      (node (ref "C32") (pin "2") (pinfunction "2_2") (pintype "passive"))
      (node (ref "L4") (pin "2") (pintype "passive"))
      (node (ref "U14") (pin "17") (pinfunction "VBUS_17") (pintype "power_in"))
      (node (ref "U14") (pin "18") (pinfunction "VBUS_18") (pintype "power_in"))
    )
    (net (code "40") (name "Net-(LED1-Pad2)") (class "Default")
      (node (ref "LED1") (pin "2") (pinfunction "2_2") (pintype "passive"))
      (node (ref "R153") (pin "1") (pinfunction "1_1") (pintype "passive"))
    )
    (net (code "41") (name "Net-(LED4-Pad2)") (class "Default")
      (node (ref "LED4") (pin "2") (pinfunction "2_2") (pintype "passive"))
      (node (ref "R53") (pin "1") (pinfunction "1_1") (pintype "passive"))
    )
    (net (code "42") (name "Net-(Q8-D)") (class "Default")
      (node (ref "Q8") (pin "3") (pinfunction "D_3") (pintype "passive"))
      (node (ref "R153") (pin "2") (pinfunction "2_2") (pintype "passive"))
    )
    (net (code "43") (name "Net-(Q9-D)") (class "Default")
      (node (ref "Q9") (pin "3") (pinfunction "D_3") (pintype "passive"))
      (node (ref "R53") (pin "2") (pinfunction "2_2") (pintype "passive"))
    )
    (net (code "44") (name "Net-(U11-~{HOLD}{slash}IO3)") (class "Default")
      (node (ref "R43") (pin "2") (pinfunction "2_2") (pintype "passive"))
      (node (ref "U11") (pin "7") (pinfunction "~{HOLD}/IO3_7") (pintype "bidirectional"))
    )
    (net (code "45") (name "Net-(U11-~{WP}{slash}IO2)") (class "Default")
      (node (ref "R42") (pin "2") (pinfunction "2_2") (pintype "passive"))
      (node (ref "U11") (pin "3") (pinfunction "~{WP}/IO2_3") (pintype "bidirectional"))
    )
    (net (code "46") (name "Net-(U14A-DEBUG_CTL1)") (class "Default")
      (node (ref "R149") (pin "2") (pinfunction "2_2") (pintype "passive"))
      (node (ref "U14") (pin "45") (pinfunction "DEBUG_CTL1_45") (pintype "bidirectional"))
    )
    (net (code "47") (name "Net-(U14A-DEBUG_CTL2)") (class "Default")
      (node (ref "R156") (pin "2") (pinfunction "2_2") (pintype "passive"))
      (node (ref "U14") (pin "44") (pinfunction "DEBUG_CTL2_44") (pintype "bidirectional"))
    )
    (net (code "48") (name "Net-(U14A-GPIO7)") (class "Default")
      (node (ref "R136") (pin "2") (pinfunction "2_2") (pintype "passive"))
      (node (ref "U14") (pin "38") (pinfunction "GPIO7_38") (pintype "bidirectional"))
    )
    (net (code "49") (name "Net-(U14A-RPD_G1)") (class "Default")
      (node (ref "R116") (pin "1") (pinfunction "1_1") (pintype "passive"))
      (node (ref "U14") (pin "12") (pinfunction "RPD_G1_12") (pintype "bidirectional"))
    )
    (net (code "50") (name "Net-(U14A-RPD_G2)") (class "Default")
      (node (ref "R120") (pin "1") (pinfunction "1_1") (pintype "passive"))
      (node (ref "U14") (pin "16") (pinfunction "RPD_G2_16") (pintype "bidirectional"))
    )
    (net (code "51") (name "Net-(U14A-R_OSC)") (class "Default")
      (node (ref "R45") (pin "2") (pinfunction "2_2") (pintype "passive"))
      (node (ref "U14") (pin "52") (pinfunction "R_OSC_52") (pintype "bidirectional"))
    )
    (net (code "52") (name "Net-(U14A-SS)") (class "Default")
      (node (ref "C30") (pin "2") (pinfunction "2_2") (pintype "passive"))
      (node (ref "U14") (pin "3") (pinfunction "SS_3") (pintype "input"))
    )
    (net (code "53") (name "Net-(U14A-SWD_CLK)") (class "Default")
      (node (ref "R148") (pin "2") (pinfunction "2_2") (pintype "passive"))
      (node (ref "U14") (pin "50") (pinfunction "SWD_CLK_50") (pintype "input"))
    )
    (net (code "54") (name "Net-(U14A-SWD_DAT)") (class "Default")
      (node (ref "R147") (pin "2") (pinfunction "2_2") (pintype "passive"))
      (node (ref "U14") (pin "49") (pinfunction "SWD_DAT_49") (pintype "bidirectional"))
    )
    (net (code "55") (name "Net-(U14B-BUSPOWER)") (class "Default")
      (node (ref "R155") (pin "1") (pinfunction "1_1") (pintype "passive"))
      (node (ref "R164") (pin "1") (pinfunction "1_1") (pintype "passive"))
      (node (ref "U14") (pin "22") (pinfunction "BUSPOWER_22") (pintype "power_in"))
    )
    (net (code "56") (name "Net-(U14B-LDO_1V8A)") (class "Default")
      (node (ref "C75") (pin "2") (pinfunction "2_2") (pintype "passive"))
      (node (ref "U14") (pin "56") (pinfunction "LDO_1V8A_56") (pintype "power_in"))
    )
    (net (code "57") (name "Net-(U14B-LDO_1V8D)") (class "Default")
      (node (ref "C74") (pin "2") (pinfunction "2_2") (pintype "passive"))
      (node (ref "U14") (pin "40") (pinfunction "LDO_1V8D_40") (pintype "power_in"))
    )
    (net (code "58") (name "Net-(U14B-LDO_BMC)") (class "Default")
      (node (ref "C100") (pin "2") (pinfunction "2_2") (pintype "passive"))
      (node (ref "U14") (pin "48") (pinfunction "LDO_BMC_48") (pintype "power_in"))
    )
    (net (code "59") (name "USB_3V3") (class "Default")
      (node (ref "C101") (pin "2") (pinfunction "2_2") (pintype "passive"))
      (node (ref "C96") (pin "2") (pinfunction "2_2") (pintype "passive"))
      (node (ref "J4") (pin "2") (pinfunction "2_2") (pintype "passive"))
      (node (ref "J7") (pin "2") (pinfunction "2_2") (pintype "passive"))
      (node (ref "R138") (pin "1") (pinfunction "1_1") (pintype "passive"))
      (node (ref "R139") (pin "1") (pinfunction "1_1") (pintype "passive"))
      (node (ref "R147") (pin "1") (pinfunction "1_1") (pintype "passive"))
      (node (ref "R150") (pin "1") (pinfunction "1_1") (pintype "passive"))
      (node (ref "R155") (pin "2") (pinfunction "2_2") (pintype "passive"))
      (node (ref "R157") (pin "1") (pinfunction "1_1") (pintype "passive"))
      (node (ref "R158") (pin "1") (pinfunction "1_1") (pintype "passive"))
      (node (ref "R42") (pin "1") (pinfunction "1_1") (pintype "passive"))
      (node (ref "R43") (pin "1") (pinfunction "1_1") (pintype "passive"))
      (node (ref "R54") (pin "2") (pinfunction "2_2") (pintype "passive"))
      (node (ref "R58") (pin "1") (pinfunction "1_1") (pintype "passive"))
      (node (ref "R59") (pin "1") (pinfunction "1_1") (pintype "passive"))
      (node (ref "U11") (pin "8") (pinfunction "VCC_8") (pintype "power_in"))
      (node (ref "U14") (pin "42") (pinfunction "VDDIO_42") (pintype "power_in"))
      (node (ref "U14") (pin "51") (pinfunction "LDO_3V3_51") (pintype "power_in"))
    )
    (net (code "60") (name "V3P3") (class "Default")
      (node (ref "LED1") (pin "1") (pinfunction "1_1") (pintype "passive"))
      (node (ref "LED4") (pin "1") (pinfunction "1_1") (pintype "passive"))
    )
    (net (code "61") (name "VBUS") (class "Default") (node (ref "L4") (pin "1") (pintype "passive")))
    (net (code "62") (name "V_USB_HV") (class "Default")
      (node (ref "C88") (pin "2") (pinfunction "2_2") (pintype "passive"))
      (node (ref "C89") (pin "2") (pinfunction "2_2") (pintype "passive"))
      (node (ref "U14") (pin "33") (pinfunction "PP_HV_33") (pintype "power_in"))
      (node (ref "U14") (pin "34") (pinfunction "PP_HV_34") (pintype "power_in"))
    )
    (net (code "63") (name "unconnected-(U14A-GPIO2-Pad25)") (class "Default")
      (node (ref "U14") (pin "25") (pinfunction "GPIO2_25") (pintype "bidirectional+no_connect"))
    )
    (net (code "64") (name "unconnected-(U14A-GPIO8-Pad1)") (class "Default")
      (node (ref "U14") (pin "1") (pinfunction "GPIO8_1") (pintype "bidirectional+no_connect"))
    )
    (net (code "65") (name "unconnected-(U14A-HV_GATE1-Pad31)") (class "Default")
      (node (ref "U14") (pin "31") (pinfunction "HV_GATE1_31") (pintype "output"))
    )
    (net (code "66") (name "unconnected-(U14A-HV_GATE2-Pad32)") (class "Default")
      (node (ref "U14") (pin "32") (pinfunction "HV_GATE2_32") (pintype "output"))
    )
    (net (code "67") (name "unconnected-(U14A-SENSEN-Pad29)") (class "Default")
      (node (ref "U14") (pin "29") (pinfunction "SENSEN_29") (pintype "input"))
    )
    (net (code "68") (name "unconnected-(U14A-SENSEP-Pad30)") (class "Default")
      (node (ref "U14") (pin "30") (pinfunction "SENSEP_30") (pintype "input"))
    )
  )
)
